# 2_mb_conn.net
KiCad netlist of a schematic drawn in Altium Designer
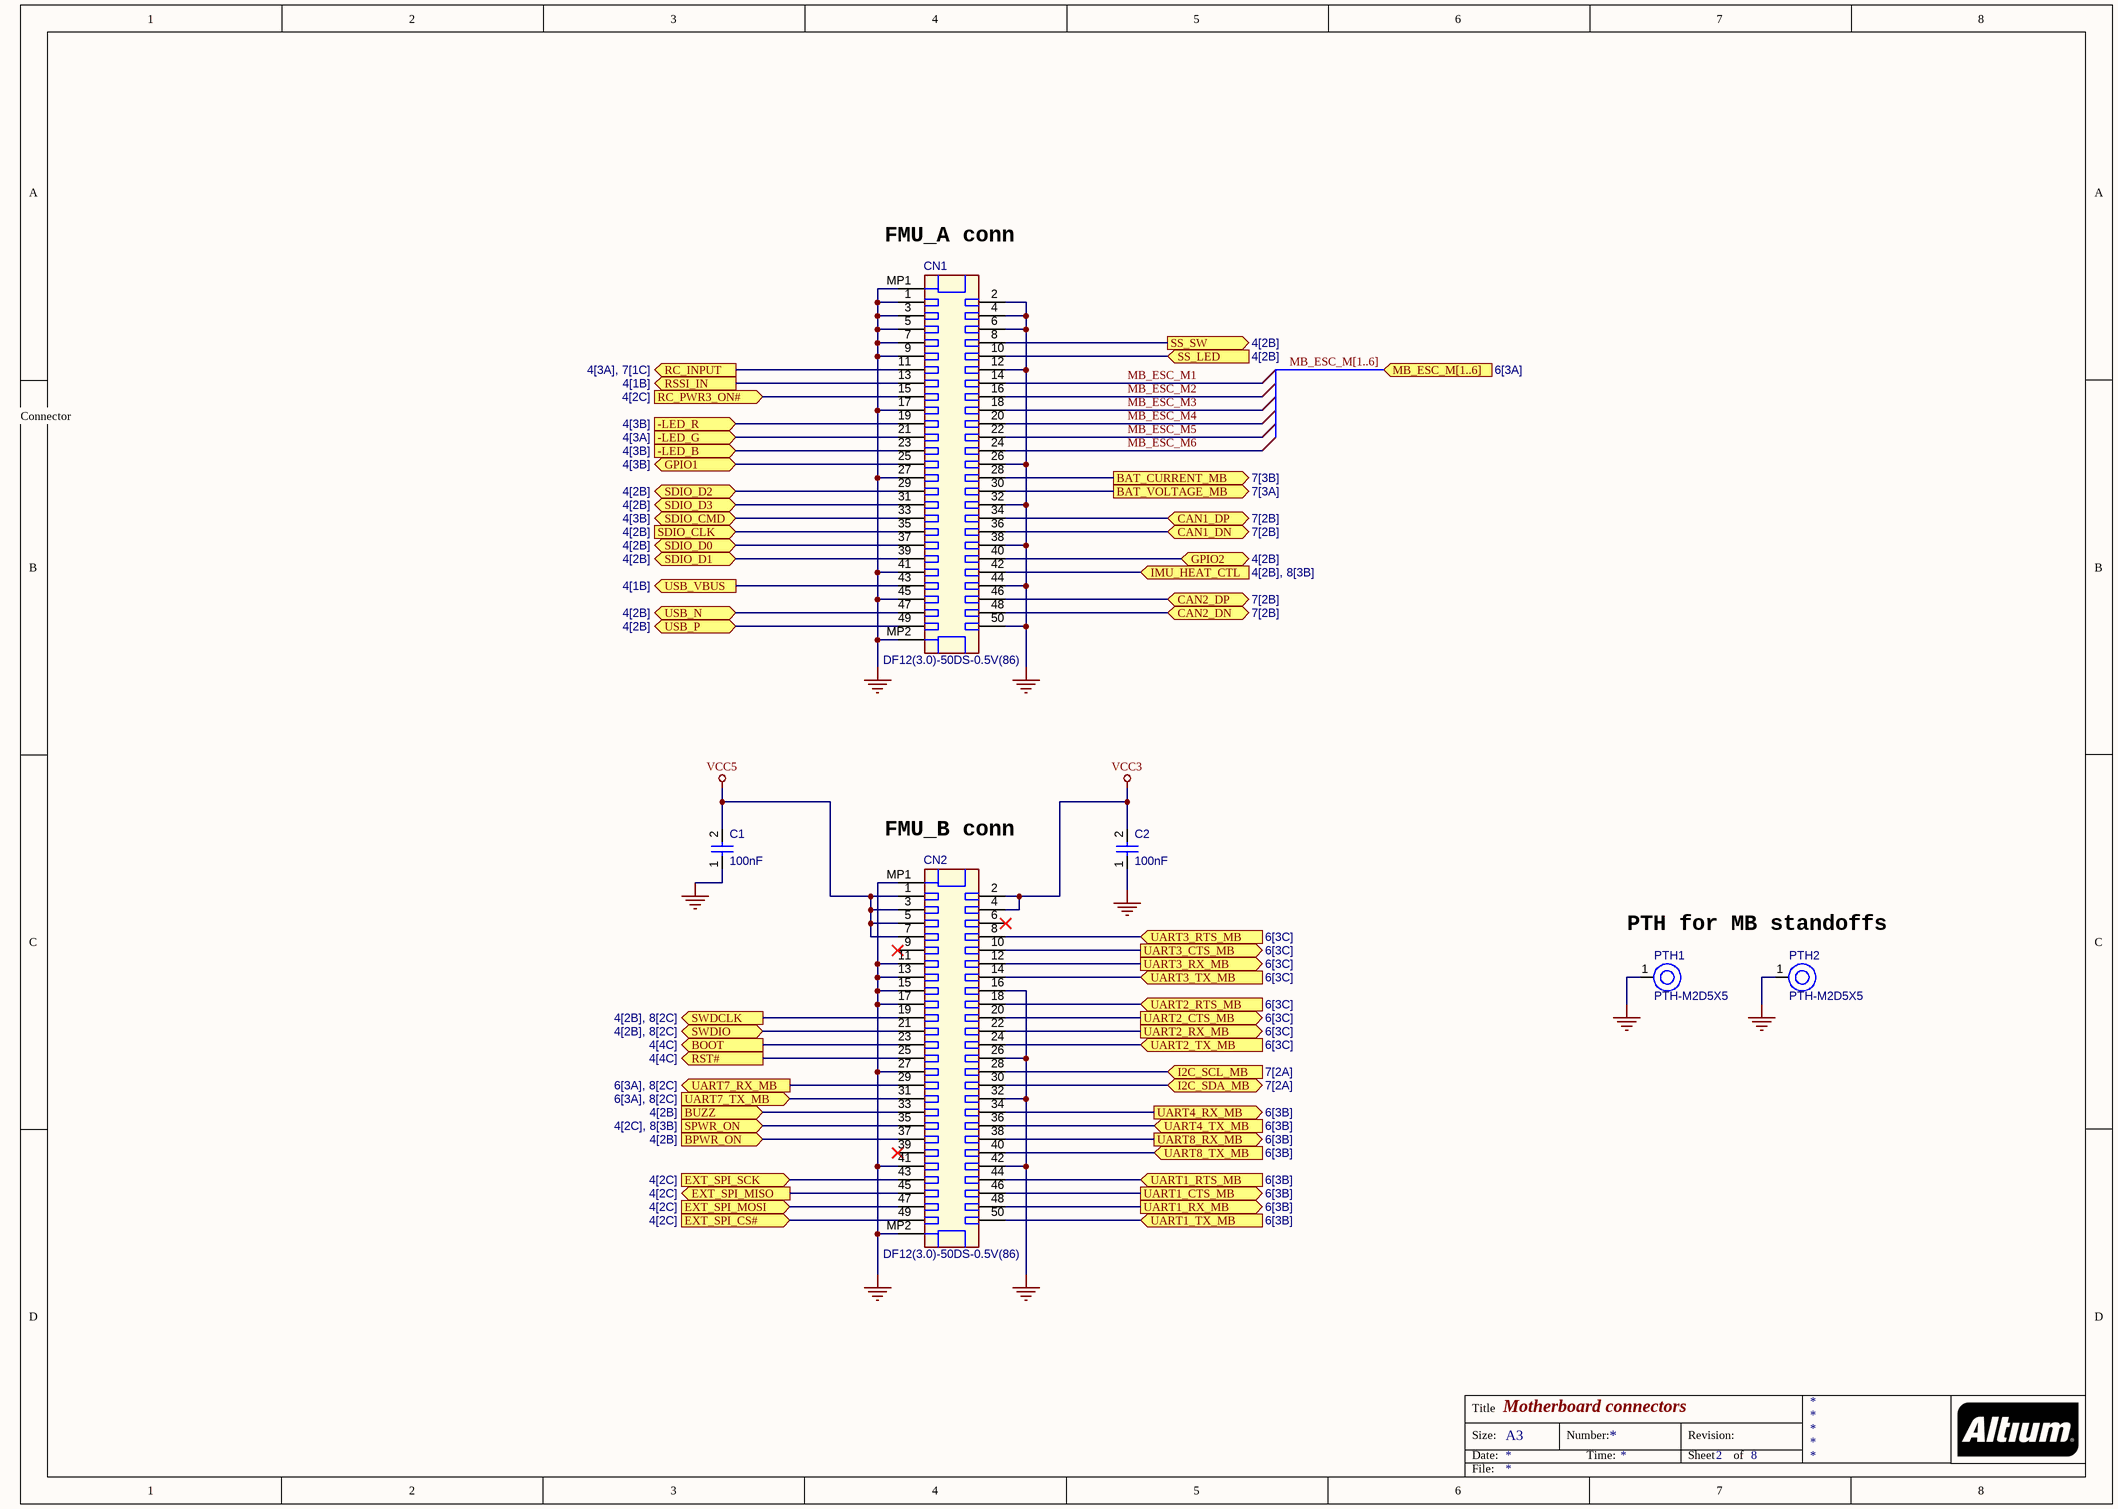
[diagram p0: 2_mb_conn.SchDoc]

(export (version "E")
  (design (tool "Eeschema 10.0.6"))
  (components
    (comp (ref "C1")
      (value "100nF")
      (footprint "CAPC0402(1005)60_L")
      (description "Chip Capacitor, 100nF +/-20%, 10V, 0402, Thickness 0.6 mm")
      (fields (field (name "TOLERANCE") "20%") (field (name "Comment") "Capacitor 100nF +/-20% 10V 0402"))
      (libsource (lib "<Company> Server") (part "CAP-NP-2"))
    )
    (comp (ref "C2")
      (value "100nF")
      (footprint "CAPC0402(1005)60_L")
      (description "Chip Capacitor, 100nF +/-20%, 10V, 0402, Thickness 0.6 mm")
      (fields (field (name "TOLERANCE") "20%") (field (name "Comment") "Capacitor 100nF +/-20% 10V 0402"))
      (libsource (lib "<Company> Server") (part "CAP-NP-2"))
    )
    (comp (ref "CN1")
      (value "DF12(3.0)-50DS-0.5V(86)")
      (footprint "HIRO-DF12(3.0)-50DS-0.5V_V")
      (description "Receptacle Connector, 50 V, 0.3 A, -45 to 125 degC, RoHS, Tape and Reel")
      (libsource (lib "<Company> Server") (part "CMP-00111-4"))
    )
    (comp (ref "CN2")
      (value "DF12(3.0)-50DS-0.5V(86)")
      (footprint "HIRO-DF12(3.0)-50DS-0.5V_V")
      (description "Receptacle Connector, 50 V, 0.3 A, -45 to 125 degC, RoHS, Tape and Reel")
      (libsource (lib "<Company> Server") (part "CMP-00111-4"))
    )
    (comp (ref "PTH1")
      (value "PTH-M2D5X5")
      (footprint "PTH-M2D5X5")
      (description "M2 PTH (2.5mm), 5mm pad")
      (libsource (lib "<Company> Server") (part "CMP-00028-00000-1"))
    )
    (comp (ref "PTH2")
      (value "PTH-M2D5X5")
      (footprint "PTH-M2D5X5")
      (description "M2 PTH (2.5mm), 5mm pad")
      (libsource (lib "<Company> Server") (part "CMP-00028-00000-1"))
    )
  )
  (nets
    (net (code "1") (name "/-LED_B") (class "Default")
      (node (ref "CN1") (pin "23") (pinfunction "23_23") (pintype "passive"))
    )
    (net (code "2") (name "/-LED_G") (class "Default")
      (node (ref "CN1") (pin "21") (pinfunction "21_21") (pintype "passive"))
    )
    (net (code "3") (name "/-LED_R") (class "Default")
      (node (ref "CN1") (pin "19") (pinfunction "19_19") (pintype "passive"))
    )
    (net (code "4") (name "/BAT_CURRENT_MB") (class "Default")
      (node (ref "CN1") (pin "28") (pinfunction "28_28") (pintype "passive"))
    )
    (net (code "5") (name "/BAT_VOLTAGE_MB") (class "Default")
      (node (ref "CN1") (pin "30") (pinfunction "30_30") (pintype "passive"))
    )
    (net (code "6") (name "/BOOT") (class "Default")
      (node (ref "CN2") (pin "23") (pinfunction "23_23") (pintype "passive"))
    )
    (net (code "7") (name "/BPWR_ON") (class "Default")
      (node (ref "CN2") (pin "37") (pinfunction "37_37") (pintype "passive"))
    )
    (net (code "8") (name "/BUZZ") (class "Default")
      (node (ref "CN2") (pin "33") (pinfunction "33_33") (pintype "passive"))
    )
    (net (code "9") (name "/CAN1_DN") (class "Default")
      (node (ref "CN1") (pin "36") (pinfunction "36_36") (pintype "passive"))
    )
    (net (code "10") (name "/CAN1_DP") (class "Default")
      (node (ref "CN1") (pin "34") (pinfunction "34_34") (pintype "passive"))
    )
    (net (code "11") (name "/CAN2_DN") (class "Default")
      (node (ref "CN1") (pin "48") (pinfunction "48_48") (pintype "passive"))
    )
    (net (code "12") (name "/CAN2_DP") (class "Default")
      (node (ref "CN1") (pin "46") (pinfunction "46_46") (pintype "passive"))
    )
    (net (code "13") (name "/EXT_SPI_CS#") (class "Default")
      (node (ref "CN2") (pin "49") (pinfunction "49_49") (pintype "passive"))
    )
    (net (code "14") (name "/EXT_SPI_MISO") (class "Default")
      (node (ref "CN2") (pin "45") (pinfunction "45_45") (pintype "passive"))
    )
    (net (code "15") (name "/EXT_SPI_MOSI") (class "Default")
      (node (ref "CN2") (pin "47") (pinfunction "47_47") (pintype "passive"))
    )
    (net (code "16") (name "/EXT_SPI_SCK") (class "Default")
      (node (ref "CN2") (pin "43") (pinfunction "43_43") (pintype "passive"))
    )
    (net (code "17") (name "/GPIO1") (class "Default")
      (node (ref "CN1") (pin "25") (pinfunction "25_25") (pintype "passive"))
    )
    (net (code "18") (name "/GPIO2") (class "Default")
      (node (ref "CN1") (pin "40") (pinfunction "40_40") (pintype "passive"))
    )
    (net (code "19") (name "/I2C_SCL_MB") (class "Default")
      (node (ref "CN2") (pin "28") (pinfunction "28_28") (pintype "passive"))
    )
    (net (code "20") (name "/I2C_SDA_MB") (class "Default")
      (node (ref "CN2") (pin "30") (pinfunction "30_30") (pintype "passive"))
    )
    (net (code "21") (name "/IMU_HEAT_CTL") (class "Default")
      (node (ref "CN1") (pin "42") (pinfunction "42_42") (pintype "passive"))
    )
    (net (code "22") (name "/MB_ESC_M1") (class "Default")
      (node (ref "CN1") (pin "14") (pinfunction "14_14") (pintype "passive"))
    )
    (net (code "23") (name "/MB_ESC_M2") (class "Default")
      (node (ref "CN1") (pin "16") (pinfunction "16_16") (pintype "passive"))
    )
    (net (code "24") (name "/MB_ESC_M3") (class "Default")
      (node (ref "CN1") (pin "18") (pinfunction "18_18") (pintype "passive"))
    )
    (net (code "25") (name "/MB_ESC_M4") (class "Default")
      (node (ref "CN1") (pin "20") (pinfunction "20_20") (pintype "passive"))
    )
    (net (code "26") (name "/MB_ESC_M5") (class "Default")
      (node (ref "CN1") (pin "22") (pinfunction "22_22") (pintype "passive"))
    )
    (net (code "27") (name "/MB_ESC_M6") (class "Default")
      (node (ref "CN1") (pin "24") (pinfunction "24_24") (pintype "passive"))
    )
    (net (code "29") (name "/RC_INPUT") (class "Default")
      (node (ref "CN1") (pin "11") (pinfunction "11_11") (pintype "passive"))
    )
    (net (code "30") (name "/RC_PWR3_ON#") (class "Default")
      (node (ref "CN1") (pin "15") (pinfunction "15_15") (pintype "passive"))
    )
    (net (code "31") (name "/RSSI_IN") (class "Default")
      (node (ref "CN1") (pin "13") (pinfunction "13_13") (pintype "passive"))
    )
    (net (code "32") (name "/RST#") (class "Default")
      (node (ref "CN2") (pin "25") (pinfunction "25_25") (pintype "passive"))
    )
    (net (code "33") (name "/SDIO_CLK") (class "Default")
      (node (ref "CN1") (pin "35") (pinfunction "35_35") (pintype "passive"))
    )
    (net (code "34") (name "/SDIO_CMD") (class "Default")
      (node (ref "CN1") (pin "33") (pinfunction "33_33") (pintype "passive"))
    )
    (net (code "35") (name "/SDIO_D0") (class "Default")
      (node (ref "CN1") (pin "37") (pinfunction "37_37") (pintype "passive"))
    )
    (net (code "36") (name "/SDIO_D1") (class "Default")
      (node (ref "CN1") (pin "39") (pinfunction "39_39") (pintype "passive"))
    )
    (net (code "37") (name "/SDIO_D2") (class "Default")
      (node (ref "CN1") (pin "29") (pinfunction "29_29") (pintype "passive"))
    )
    (net (code "38") (name "/SDIO_D3") (class "Default")
      (node (ref "CN1") (pin "31") (pinfunction "31_31") (pintype "passive"))
    )
    (net (code "39") (name "/SPWR_ON") (class "Default")
      (node (ref "CN2") (pin "35") (pinfunction "35_35") (pintype "passive"))
    )
    (net (code "40") (name "/SS_LED") (class "Default")
      (node (ref "CN1") (pin "10") (pinfunction "10_10") (pintype "passive"))
    )
    (net (code "41") (name "/SS_SW") (class "Default")
      (node (ref "CN1") (pin "8") (pinfunction "8_8") (pintype "passive"))
    )
    (net (code "42") (name "/SWDCLK") (class "Default")
      (node (ref "CN2") (pin "19") (pinfunction "19_19") (pintype "passive"))
    )
    (net (code "43") (name "/SWDIO") (class "Default")
      (node (ref "CN2") (pin "21") (pinfunction "21_21") (pintype "passive"))
    )
    (net (code "44") (name "/UART1_CTS_MB") (class "Default")
      (node (ref "CN2") (pin "46") (pinfunction "46_46") (pintype "passive"))
    )
    (net (code "45") (name "/UART1_RTS_MB") (class "Default")
      (node (ref "CN2") (pin "44") (pinfunction "44_44") (pintype "passive"))
    )
    (net (code "46") (name "/UART1_RX_MB") (class "Default")
      (node (ref "CN2") (pin "48") (pinfunction "48_48") (pintype "passive"))
    )
    (net (code "47") (name "/UART1_TX_MB") (class "Default")
      (node (ref "CN2") (pin "50") (pinfunction "50_50") (pintype "passive"))
    )
    (net (code "48") (name "/UART2_CTS_MB") (class "Default")
      (node (ref "CN2") (pin "20") (pinfunction "20_20") (pintype "passive"))
    )
    (net (code "49") (name "/UART2_RTS_MB") (class "Default")
      (node (ref "CN2") (pin "18") (pinfunction "18_18") (pintype "passive"))
    )
    (net (code "50") (name "/UART2_RX_MB") (class "Default")
      (node (ref "CN2") (pin "22") (pinfunction "22_22") (pintype "passive"))
    )
    (net (code "51") (name "/UART2_TX_MB") (class "Default")
      (node (ref "CN2") (pin "24") (pinfunction "24_24") (pintype "passive"))
    )
    (net (code "52") (name "/UART3_CTS_MB") (class "Default")
      (node (ref "CN2") (pin "10") (pinfunction "10_10") (pintype "passive"))
    )
    (net (code "53") (name "/UART3_RTS_MB") (class "Default")
      (node (ref "CN2") (pin "8") (pinfunction "8_8") (pintype "passive"))
    )
    (net (code "54") (name "/UART3_RX_MB") (class "Default")
      (node (ref "CN2") (pin "12") (pinfunction "12_12") (pintype "passive"))
    )
    (net (code "55") (name "/UART3_TX_MB") (class "Default")
      (node (ref "CN2") (pin "14") (pinfunction "14_14") (pintype "passive"))
    )
    (net (code "56") (name "/UART4_RX_MB") (class "Default")
      (node (ref "CN2") (pin "34") (pinfunction "34_34") (pintype "passive"))
    )
    (net (code "57") (name "/UART4_TX_MB") (class "Default")
      (node (ref "CN2") (pin "36") (pinfunction "36_36") (pintype "passive"))
    )
    (net (code "58") (name "/UART7_RX_MB") (class "Default")
      (node (ref "CN2") (pin "29") (pinfunction "29_29") (pintype "passive"))
    )
    (net (code "59") (name "/UART7_TX_MB") (class "Default")
      (node (ref "CN2") (pin "31") (pinfunction "31_31") (pintype "passive"))
    )
    (net (code "60") (name "/UART8_RX_MB") (class "Default")
      (node (ref "CN2") (pin "38") (pinfunction "38_38") (pintype "passive"))
    )
    (net (code "61") (name "/UART8_TX_MB") (class "Default")
      (node (ref "CN2") (pin "40") (pinfunction "40_40") (pintype "passive"))
    )
    (net (code "62") (name "/USB_N") (class "Default")
      (node (ref "CN1") (pin "47") (pinfunction "47_47") (pintype "passive"))
    )
    (net (code "63") (name "/USB_P") (class "Default")
      (node (ref "CN1") (pin "49") (pinfunction "49_49") (pintype "passive"))
    )
    (net (code "64") (name "/USB_VBUS") (class "Default")
      (node (ref "CN1") (pin "43") (pinfunction "43_43") (pintype "passive"))
    )
    (net (code "65") (name "GND") (class "Default")
      (node (ref "C1") (pin "1") (pinfunction "1_1") (pintype "passive"))
      (node (ref "C2") (pin "1") (pinfunction "1_1") (pintype "passive"))
      (node (ref "CN1") (pin "1") (pinfunction "1_1") (pintype "passive"))
      (node (ref "CN1") (pin "12") (pinfunction "12_12") (pintype "passive"))
      (node (ref "CN1") (pin "17") (pinfunction "17_17") (pintype "passive"))
      (node (ref "CN1") (pin "2") (pinfunction "2_2") (pintype "passive"))
      (node (ref "CN1") (pin "26") (pinfunction "26_26") (pintype "passive"))
      (node (ref "CN1") (pin "27") (pinfunction "27_27") (pintype "passive"))
      (node (ref "CN1") (pin "3") (pinfunction "3_3") (pintype "passive"))
      (node (ref "CN1") (pin "32") (pinfunction "32_32") (pintype "passive"))
      (node (ref "CN1") (pin "38") (pinfunction "38_38") (pintype "passive"))
      (node (ref "CN1") (pin "4") (pinfunction "4_4") (pintype "passive"))
      (node (ref "CN1") (pin "41") (pinfunction "41_41") (pintype "passive"))
      (node (ref "CN1") (pin "44") (pinfunction "44_44") (pintype "passive"))
      (node (ref "CN1") (pin "45") (pinfunction "45_45") (pintype "passive"))
      (node (ref "CN1") (pin "5") (pinfunction "5_5") (pintype "passive"))
      (node (ref "CN1") (pin "50") (pinfunction "50_50") (pintype "passive"))
      (node (ref "CN1") (pin "6") (pinfunction "6_6") (pintype "passive"))
      (node (ref "CN1") (pin "7") (pinfunction "7_7") (pintype "passive"))
      (node (ref "CN1") (pin "9") (pinfunction "9_9") (pintype "passive"))
      (node (ref "CN1") (pin "MP1") (pinfunction "MP1_MP1") (pintype "passive"))
      (node (ref "CN1") (pin "MP2") (pinfunction "MP2_MP2") (pintype "passive"))
      (node (ref "CN2") (pin "11") (pinfunction "11_11") (pintype "passive"))
      (node (ref "CN2") (pin "13") (pinfunction "13_13") (pintype "passive"))
      (node (ref "CN2") (pin "15") (pinfunction "15_15") (pintype "passive"))
      (node (ref "CN2") (pin "16") (pinfunction "16_16") (pintype "passive"))
      (node (ref "CN2") (pin "17") (pinfunction "17_17") (pintype "passive"))
      (node (ref "CN2") (pin "26") (pinfunction "26_26") (pintype "passive"))
      (node (ref "CN2") (pin "27") (pinfunction "27_27") (pintype "passive"))
      (node (ref "CN2") (pin "32") (pinfunction "32_32") (pintype "passive"))
      (node (ref "CN2") (pin "41") (pinfunction "41_41") (pintype "passive"))
      (node (ref "CN2") (pin "42") (pinfunction "42_42") (pintype "passive"))
      (node (ref "CN2") (pin "MP1") (pinfunction "MP1_MP1") (pintype "passive"))
      (node (ref "CN2") (pin "MP2") (pinfunction "MP2_MP2") (pintype "passive"))
      (node (ref "PTH1") (pin "1") (pinfunction "H1_1") (pintype "passive"))
      (node (ref "PTH2") (pin "1") (pinfunction "H1_1") (pintype "passive"))
    )
    (net (code "66") (name "VCC3") (class "Default")
      (node (ref "C2") (pin "2") (pinfunction "2_2") (pintype "passive"))
      (node (ref "CN2") (pin "2") (pinfunction "2_2") (pintype "passive"))
      (node (ref "CN2") (pin "4") (pinfunction "4_4") (pintype "passive"))
    )
    (net (code "67") (name "VCC5") (class "Default")
      (node (ref "C1") (pin "2") (pinfunction "2_2") (pintype "passive"))
      (node (ref "CN2") (pin "1") (pinfunction "1_1") (pintype "passive"))
      (node (ref "CN2") (pin "3") (pinfunction "3_3") (pintype "passive"))
      (node (ref "CN2") (pin "5") (pinfunction "5_5") (pintype "passive"))
      (node (ref "CN2") (pin "7") (pinfunction "7_7") (pintype "passive"))
    )
    (net (code "68") (name "unconnected-(CN2-Pad6)") (class "Default")
      (node (ref "CN2") (pin "6") (pinfunction "6_6") (pintype "passive+no_connect"))
    )
    (net (code "69") (name "unconnected-(CN2-Pad9)") (class "Default")
      (node (ref "CN2") (pin "9") (pinfunction "9_9") (pintype "passive+no_connect"))
    )
    (net (code "70") (name "unconnected-(CN2-Pad39)") (class "Default")
      (node (ref "CN2") (pin "39") (pinfunction "39_39") (pintype "passive+no_connect"))
    )
  )
)
